# agent-mother.net
KiCad netlist of a schematic drawn in Altium Designer
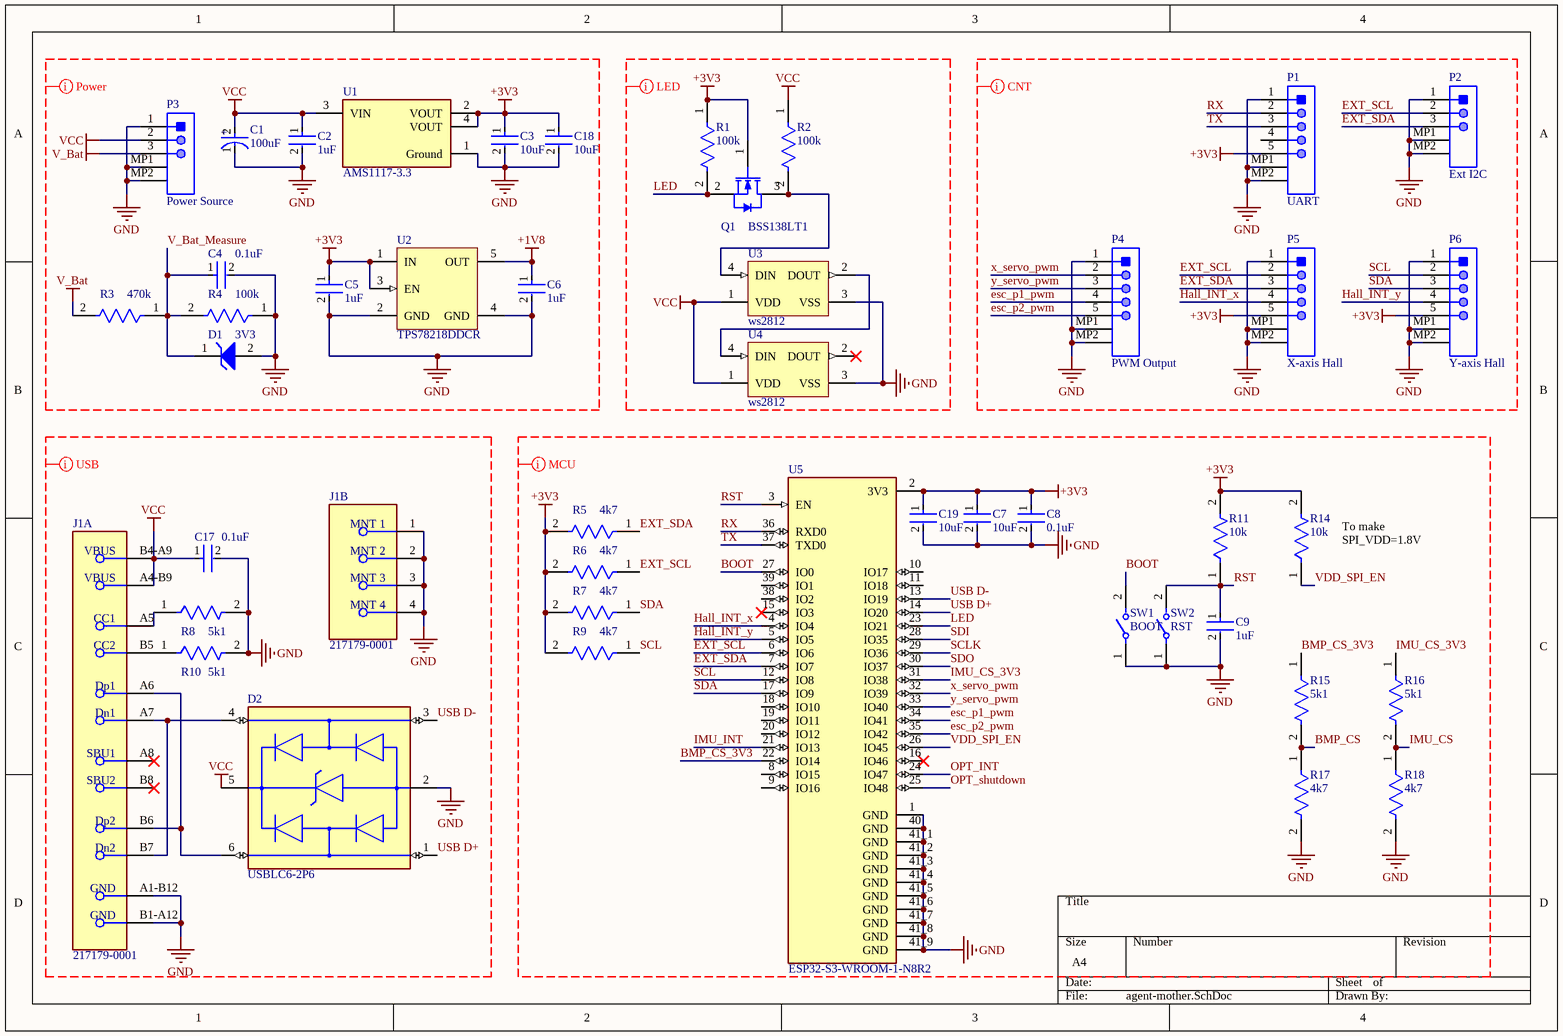
[diagram p0: agent-mother.SchDoc]

(export (version "E")
  (design (tool "Eeschema 10.0.6"))
  (components
    (comp (ref "C1")
      (value "100uF")
      (footprint "FP-T495D107K016ATE125-MFG")
      (description "CAP TANT 100UF 10% 16V 2917")
      (fields (field (name "VOLTAGE") "16V") (field (name "TOLERANCE") "10%"))
      (libsource (lib "Altium Content Vault") (part "a00bbbee19879c290e62620ae7e47b1"))
    )
    (comp (ref "C2")
      (value "1uF")
      (footprint "FP-C0402-BB-MFG")
      (description "CAP CER 1uF 16V X7R 0402")
      (fields
        (field (name "TOLERANCE") "0.1")
        (field (name "OCTOPART") "https://octopart.com/c0402c104k4ractu-kemet-94158")
      )
      (libsource (lib "Altium Content Vault") (part "b4654b650e69147ec39a6b967a45e02"))
    )
    (comp (ref "C3")
      (value "10uF")
      (footprint "FP-C0402-BB-MFG")
      (description "CAP CER 22uF 16V X7R 0402")
      (fields
        (field (name "TOLERANCE") "0.1")
        (field (name "OCTOPART") "https://octopart.com/c0402c104k4ractu-kemet-94158")
      )
      (libsource (lib "Altium Content Vault") (part "b4654b650e69147ec39a6b967a45e02"))
    )
    (comp (ref "C4")
      (value "0.1uF")
      (footprint "FP-C0402-BB-MFG")
      (description "CAP CER 0.1uF 16V X7R 0402")
      (fields
        (field (name "TOLERANCE") "0.1")
        (field (name "OCTOPART") "https://octopart.com/c0402c104k4ractu-kemet-94158")
      )
      (libsource (lib "Altium Content Vault") (part "b4654b650e69147ec39a6b967a45e02"))
    )
    (comp (ref "C5")
      (value "1uF")
      (footprint "FP-C0402-BB-MFG")
      (description "CAP CER 1uF 16V X7R 0402")
      (fields
        (field (name "TOLERANCE") "0.1")
        (field (name "OCTOPART") "https://octopart.com/c0402c104k4ractu-kemet-94158")
      )
      (libsource (lib "Altium Content Vault") (part "b4654b650e69147ec39a6b967a45e02"))
    )
    (comp (ref "C6")
      (value "1uF")
      (footprint "FP-C0402-BB-MFG")
      (description "CAP CER 1uF 16V X7R 0402")
      (fields
        (field (name "TOLERANCE") "0.1")
        (field (name "OCTOPART") "https://octopart.com/c0402c104k4ractu-kemet-94158")
      )
      (libsource (lib "Altium Content Vault") (part "b4654b650e69147ec39a6b967a45e02"))
    )
    (comp (ref "C7")
      (value "10uF")
      (footprint "FP-C0402-BB-MFG")
      (description "CAP CER 22uF 16V X7R 0402")
      (fields
        (field (name "TOLERANCE") "0.1")
        (field (name "OCTOPART") "https://octopart.com/c0402c104k4ractu-kemet-94158")
      )
      (libsource (lib "Altium Content Vault") (part "b4654b650e69147ec39a6b967a45e02"))
    )
    (comp (ref "C8")
      (value "0.1uF")
      (footprint "FP-C0402-BB-MFG")
      (description "CAP CER 0.1uF 16V X7R 0402")
      (fields
        (field (name "TOLERANCE") "0.1")
        (field (name "OCTOPART") "https://octopart.com/c0402c104k4ractu-kemet-94158")
      )
      (libsource (lib "Altium Content Vault") (part "b4654b650e69147ec39a6b967a45e02"))
    )
    (comp (ref "C9")
      (value "1uF")
      (footprint "FP-C0402-BB-MFG")
      (description "CAP CER 1uF 16V X7R 0402")
      (fields
        (field (name "TOLERANCE") "0.1")
        (field (name "OCTOPART") "https://octopart.com/c0402c104k4ractu-kemet-94158")
      )
      (libsource (lib "Altium Content Vault") (part "b4654b650e69147ec39a6b967a45e02"))
    )
    (comp (ref "C17")
      (value "0.1uF")
      (footprint "FP-C0402-BB-MFG")
      (description "CAP CER 0.1uF 16V X7R 0402")
      (fields
        (field (name "TOLERANCE") "0.1")
        (field (name "OCTOPART") "https://octopart.com/c0402c104k4ractu-kemet-94158")
      )
      (libsource (lib "Altium Content Vault") (part "b4654b650e69147ec39a6b967a45e02"))
    )
    (comp (ref "C18")
      (value "10uF")
      (footprint "FP-C0402-BB-MFG")
      (description "CAP CER 22uF 16V X7R 0402")
      (fields
        (field (name "TOLERANCE") "0.1")
        (field (name "OCTOPART") "https://octopart.com/c0402c104k4ractu-kemet-94158")
      )
      (libsource (lib "Altium Content Vault") (part "b4654b650e69147ec39a6b967a45e02"))
    )
    (comp (ref "C19")
      (value "10uF")
      (footprint "FP-C0402-BB-MFG")
      (description "CAP CER 22uF 16V X7R 0402")
      (fields
        (field (name "TOLERANCE") "0.1")
        (field (name "OCTOPART") "https://octopart.com/c0402c104k4ractu-kemet-94158")
      )
      (libsource (lib "Altium Content Vault") (part "b4654b650e69147ec39a6b967a45e02"))
    )
    (comp (ref "D1")
      (value "3V3")
      (footprint "ONSC-SOD-323-2-477-02_V")
      (description "Zener Voltage Regulator, 300 mW, 2-Pin SOD-323, Pb-Free, Tape and Reel")
      (fields (field (name "PARTNUMBER") "MM3Z3V3T1G") (field (name "MANUFACTURER") "On Semiconductor"))
      (libsource (lib "Altium Content Vault") (part "ONSC-K1A2-2"))
    )
    (comp (ref "D2")
      (value "USBLC6-2P6")
      (footprint "SOT-23-6 USBLC6")
      (description "TVS DIODE 5.25V 17V SOT666")
      (libsource (lib "TVMD") (part "USBLC6-2P6"))
    )
    (comp (ref "J1")
      (value "217179-0001")
      (footprint "FP-217179-0001-MFG")
      (description "CONN RCP USB2.0 TYP C 24P SMD RA")
      (libsource (lib "Altium Content Vault") (part "5f86746d156db037abd23105bb3dbc5"))
    )
    (comp (ref "P1")
      (value "UART")
      (footprint "MOLX-52361-0571-5_V")
      (description "Male Header, Pitch 1.25 mm, 1 x 5 Position, Height 3.4 mm, RoHS, Tape and Reel")
      (fields (field (name "MANUFACTURER") "Molex"))
      (libsource (lib "Altium Content Vault") (part "CN-1P-2M-R5"))
    )
    (comp (ref "P2")
      (value "Ext I2C")
      (footprint "FP-53261-0371-MFG")
      (description "CONN HEADER SMD R/A 3POS 1.25MM")
      (fields
        (field (name "MANUFACTURER") "Molex")
        (field (name "OCTOPART") "https://octopart.com/53261-0371-molex-655314")
      )
      (libsource (lib "Components - 19.08.23 - 20.17") (part "CMP-04776-000071-1"))
    )
    (comp (ref "P3")
      (value "Power Source")
      (footprint "FP-53261-0371-MFG")
      (description "CONN HEADER SMD R/A 3POS 1.25MM")
      (fields
        (field (name "MANUFACTURER") "Molex")
        (field (name "OCTOPART") "https://octopart.com/53261-0371-molex-655314")
      )
      (libsource (lib "Components - 19.08.23 - 20.17") (part "CMP-04776-000071-1"))
    )
    (comp (ref "P4")
      (value "PWM Output")
      (footprint "MOLX-52361-0571-5_V")
      (description "Male Header, Pitch 1.25 mm, 1 x 5 Position, Height 3.4 mm, RoHS, Tape and Reel")
      (fields (field (name "MANUFACTURER") "Molex"))
      (libsource (lib "Altium Content Vault") (part "CN-1P-2M-R5"))
    )
    (comp (ref "P5")
      (value "X-axis Hall")
      (footprint "MOLX-52361-0571-5_V")
      (description "Male Header, Pitch 1.25 mm, 1 x 5 Position, Height 3.4 mm, RoHS, Tape and Reel")
      (fields (field (name "MANUFACTURER") "Molex"))
      (libsource (lib "Altium Content Vault") (part "CN-1P-2M-R5"))
    )
    (comp (ref "P6")
      (value "Y-axis Hall")
      (footprint "MOLX-52361-0571-5_V")
      (description "Male Header, Pitch 1.25 mm, 1 x 5 Position, Height 3.4 mm, RoHS, Tape and Reel")
      (fields (field (name "MANUFACTURER") "Molex"))
      (libsource (lib "Altium Content Vault") (part "CN-1P-2M-R5"))
    )
    (comp (ref "Q1")
      (value "BSS138LT1")
      (footprint "ONSC-SOT-23-3-318-08_V")
      (description "Power MOSFET, BSS138LT1, 200 mA, 50 V, N-Channel, 3-Pin SOT-23, Tape and Reel")
      (fields (field (name "MANUFACTURER") "On Semiconductor"))
      (libsource (lib "Altium Content Vault") (part "ONSC-NMOS-G1S2D3-3"))
    )
    (comp (ref "R1")
      (value "100k")
      (footprint "FP-CRCW0402-e3-IPC_A")
      (description "RES Thick Film, 100kΩ, 0.063W, 0402")
      (fields (field (name "TOLERANCE") "5%"))
      (libsource (lib "Altium Content Vault") (part "1029c3af85768c4190bb7ad29bc67b5"))
    )
    (comp (ref "R2")
      (value "100k")
      (footprint "FP-CRCW0402-e3-IPC_A")
      (description "RES Thick Film, 100kΩ, 0.063W, 0402")
      (fields (field (name "TOLERANCE") "5%"))
      (libsource (lib "Altium Content Vault") (part "1029c3af85768c4190bb7ad29bc67b5"))
    )
    (comp (ref "R3")
      (value "470k")
      (footprint "FP-CRCW0402-e3-IPC_A")
      (description "RES Thick Film, 100kΩ, 0.063W, 0402")
      (fields (field (name "TOLERANCE") "5%"))
      (libsource (lib "Altium Content Vault") (part "1029c3af85768c4190bb7ad29bc67b5"))
    )
    (comp (ref "R4")
      (value "100k")
      (footprint "FP-CRCW0402-e3-IPC_A")
      (description "RES Thick Film, 470kΩ, 0.063W, 0402")
      (fields (field (name "TOLERANCE") "5%"))
      (libsource (lib "Altium Content Vault") (part "1029c3af85768c4190bb7ad29bc67b5"))
    )
    (comp (ref "R5")
      (value "4k7")
      (footprint "FP-CRCW0402-e3-IPC_A")
      (description "RES Thick Film, 4k7Ω, 0.063W, 0402")
      (fields (field (name "TOLERANCE") "5%"))
      (libsource (lib "Altium Content Vault") (part "1029c3af85768c4190bb7ad29bc67b5"))
    )
    (comp (ref "R6")
      (value "4k7")
      (footprint "FP-CRCW0402-e3-IPC_A")
      (description "RES Thick Film, 4k7Ω, 0.063W, 0402")
      (fields (field (name "TOLERANCE") "5%"))
      (libsource (lib "Altium Content Vault") (part "1029c3af85768c4190bb7ad29bc67b5"))
    )
    (comp (ref "R7")
      (value "4k7")
      (footprint "FP-CRCW0402-e3-IPC_A")
      (description "RES Thick Film, 4k7Ω, 0.063W, 0402")
      (fields (field (name "TOLERANCE") "5%"))
      (libsource (lib "Altium Content Vault") (part "1029c3af85768c4190bb7ad29bc67b5"))
    )
    (comp (ref "R8")
      (value "5k1")
      (footprint "FP-CRCW0402-e3-IPC_A")
      (description "RES Thick Film, 5k1Ω, 0.063W, 0402")
      (fields (field (name "TOLERANCE") "5%"))
      (libsource (lib "Altium Content Vault") (part "1029c3af85768c4190bb7ad29bc67b5"))
    )
    (comp (ref "R9")
      (value "4k7")
      (footprint "FP-CRCW0402-e3-IPC_A")
      (description "RES Thick Film, 4k7Ω, 0.063W, 0402")
      (fields (field (name "TOLERANCE") "5%"))
      (libsource (lib "Altium Content Vault") (part "1029c3af85768c4190bb7ad29bc67b5"))
    )
    (comp (ref "R10")
      (value "5k1")
      (footprint "FP-CRCW0402-e3-IPC_A")
      (description "RES Thick Film, 5k1Ω, 0.063W, 0402")
      (fields (field (name "TOLERANCE") "5%"))
      (libsource (lib "Altium Content Vault") (part "1029c3af85768c4190bb7ad29bc67b5"))
    )
    (comp (ref "R11")
      (value "10k")
      (footprint "FP-CRCW0402-e3-IPC_A")
      (description "RES Thick Film, 10kΩ, 0.063W, 0402")
      (fields (field (name "TOLERANCE") "5%"))
      (libsource (lib "Altium Content Vault") (part "1029c3af85768c4190bb7ad29bc67b5"))
    )
    (comp (ref "R14")
      (value "10k")
      (footprint "FP-CRCW0402-e3-IPC_A")
      (description "RES Thick Film, 10kΩ, 0.063W, 0402")
      (fields (field (name "TOLERANCE") "5%"))
      (libsource (lib "Altium Content Vault") (part "1029c3af85768c4190bb7ad29bc67b5"))
    )
    (comp (ref "R15")
      (value "5k1")
      (footprint "FP-CRCW0402-e3-IPC_A")
      (description "RES Thick Film, 4k7Ω, 0.063W, 0402")
      (fields (field (name "TOLERANCE") "5%"))
      (libsource (lib "Altium Content Vault") (part "1029c3af85768c4190bb7ad29bc67b5"))
    )
    (comp (ref "R16")
      (value "5k1")
      (footprint "FP-CRCW0402-e3-IPC_A")
      (description "RES Thick Film, 4k7Ω, 0.063W, 0402")
      (fields (field (name "TOLERANCE") "5%"))
      (libsource (lib "Altium Content Vault") (part "1029c3af85768c4190bb7ad29bc67b5"))
    )
    (comp (ref "R17")
      (value "4k7")
      (footprint "FP-CRCW0402-e3-IPC_A")
      (description "RES Thick Film, 4k7Ω, 0.063W, 0402")
      (fields (field (name "TOLERANCE") "5%"))
      (libsource (lib "Altium Content Vault") (part "1029c3af85768c4190bb7ad29bc67b5"))
    )
    (comp (ref "R18")
      (value "4k7")
      (footprint "FP-CRCW0402-e3-IPC_A")
      (description "RES Thick Film, 4k7Ω, 0.063W, 0402")
      (fields (field (name "TOLERANCE") "5%"))
      (libsource (lib "Altium Content Vault") (part "1029c3af85768c4190bb7ad29bc67b5"))
    )
    (comp (ref "SW1")
      (value "BOOT")
      (footprint "FP-B3U-1000P-B-MFG")
      (description "SWITCH TACTILE SPST-NO 0.05A 12V")
      (fields
        (field (name "MANUFACTURER PART NUMBER") "B3U-1000P-B")
        (field (name "OCTOPART") "https://octopart.com/b3u-1000p-b-omron-1057356")
      )
      (libsource (lib "Altium Content Vault") (part "bb27bde45df87f1f469753f287ef5ae"))
    )
    (comp (ref "SW2")
      (value "RST")
      (footprint "FP-B3U-1000P-B-MFG")
      (description "SWITCH TACTILE SPST-NO 0.05A 12V")
      (fields
        (field (name "MANUFACTURER PART NUMBER") "B3U-1000P-B")
        (field (name "OCTOPART") "https://octopart.com/b3u-1000p-b-omron-1057356")
      )
      (libsource (lib "Altium Content Vault") (part "bb27bde45df87f1f469753f287ef5ae"))
    )
    (comp (ref "U1")
      (value "AMS1117-3.3")
      (footprint "FP-AMS1117-IPC_A")
      (description "LDO Voltage Regulators 1A, 3.3V")
      (fields
        (field (name "OCTOPART") "https://octopart.com/ams1117-3.3-advanced+monolithic+systems-25899300")
        (field (name "MANUFACTURER") "Advanced Monolithic Systems")
      )
      (libsource (lib "Altium Content Vault") (part "8bdbb5f8e77002000e30dd2845d0354"))
    )
    (comp (ref "U2")
      (value "TPS78218DDCR")
      (footprint "SOT-23-OT5_M")
      (fields (field (name "MANUFACTURER") "Texas Instruments") (field (name "PARTNUMBER") "TPS78218DRVR"))
      (libsource (lib "TVMD") (part "TI-TPS782XXDRV6-1600X1000TP"))
    )
    (comp (ref "U3")
      (value "ws2812")
      (footprint "ADA-RGB-1655_V")
      (fields (field (name "MANUFACTURER") "Adafruit-Industries-LLC"))
      (libsource (lib "Altium Content Vault") (part "ADA-RGB-1655-4"))
    )
    (comp (ref "U4")
      (value "ws2812")
      (footprint "ADA-RGB-1655_V")
      (fields (field (name "MANUFACTURER") "Adafruit-Industries-LLC"))
      (libsource (lib "Altium Content Vault") (part "ADA-RGB-1655-4"))
    )
    (comp (ref "U5")
      (value "ESP32-S3-WROOM-1-N8R2")
      (footprint "XCVR_ESP32S3WROOM1N8R8")
      (description "Bluetooth, WiFi 802.11b/g/n, Bluetooth v5.0 Transceiver Module 2.4GHz PCB Trace Surface Mount")
      (fields (field (name "MF") "Espressif Systems") (field (name "MP") "ESP32-S3-WROOM-1-N8R8"))
      (libsource (lib "ESP32-S3-WROOM-1-N8R8") (part "ESP32-S3-WROOM-1-N8R8"))
    )
  )
  (nets
    (net (code "1") (name "+1V8") (class "Default")
      (node (ref "C6") (pin "1") (pinfunction "1_1") (pintype "passive"))
      (node (ref "U2") (pin "5") (pinfunction "OUT_5") (pintype "power_in"))
    )
    (net (code "2") (name "+3V3") (class "Default")
      (node (ref "C18") (pin "1") (pinfunction "1_1") (pintype "passive"))
      (node (ref "C19") (pin "1") (pinfunction "1_1") (pintype "passive"))
      (node (ref "C3") (pin "1") (pinfunction "1_1") (pintype "passive"))
      (node (ref "C5") (pin "1") (pinfunction "1_1") (pintype "passive"))
      (node (ref "C7") (pin "1") (pinfunction "1_1") (pintype "passive"))
      (node (ref "C8") (pin "1") (pinfunction "1_1") (pintype "passive"))
      (node (ref "P1") (pin "5") (pinfunction "5_5") (pintype "passive"))
      (node (ref "P5") (pin "5") (pinfunction "5_5") (pintype "passive"))
      (node (ref "P6") (pin "5") (pinfunction "5_5") (pintype "passive"))
      (node (ref "Q1") (pin "1") (pinfunction "G_1") (pintype "passive"))
      (node (ref "R1") (pin "1") (pinfunction "1_1") (pintype "passive"))
      (node (ref "R11") (pin "2") (pinfunction "2_2") (pintype "passive"))
      (node (ref "R14") (pin "2") (pinfunction "2_2") (pintype "passive"))
      (node (ref "R5") (pin "2") (pinfunction "2_2") (pintype "passive"))
      (node (ref "R6") (pin "2") (pinfunction "2_2") (pintype "passive"))
      (node (ref "R7") (pin "2") (pinfunction "2_2") (pintype "passive"))
      (node (ref "R9") (pin "2") (pinfunction "2_2") (pintype "passive"))
      (node (ref "U1") (pin "2") (pinfunction "VOUT_2") (pintype "passive"))
      (node (ref "U1") (pin "4") (pinfunction "VOUT_4") (pintype "passive"))
      (node (ref "U2") (pin "1") (pinfunction "IN_1") (pintype "power_in"))
      (node (ref "U2") (pin "3") (pinfunction "EN_3") (pintype "input"))
      (node (ref "U5") (pin "2") (pinfunction "3V3_2") (pintype "power_in"))
    )
    (net (code "3") (name "/BMP_CS") (class "Default")
      (node (ref "R15") (pin "2") (pinfunction "2_2") (pintype "passive"))
      (node (ref "R17") (pin "1") (pinfunction "1_1") (pintype "passive"))
    )
    (net (code "4") (name "/BMP_CS_3V3") (class "Default")
      (node (ref "R15") (pin "1") (pinfunction "1_1") (pintype "passive"))
      (node (ref "U5") (pin "22") (pinfunction "IO14_22") (pintype "bidirectional"))
    )
    (net (code "5") (name "/BOOT") (class "Default")
      (node (ref "SW1") (pin "2") (pinfunction "2_2") (pintype "passive"))
      (node (ref "U5") (pin "27") (pinfunction "IO0_27") (pintype "bidirectional"))
    )
    (net (code "6") (name "/EXT_SCL") (class "Default")
      (node (ref "P2") (pin "2") (pinfunction "2_2") (pintype "passive"))
      (node (ref "P5") (pin "2") (pinfunction "2_2") (pintype "passive"))
      (node (ref "R6") (pin "1") (pinfunction "1_1") (pintype "passive"))
      (node (ref "U5") (pin "6") (pinfunction "IO6_6") (pintype "bidirectional"))
    )
    (net (code "7") (name "/EXT_SDA") (class "Default")
      (node (ref "P2") (pin "3") (pinfunction "3_3") (pintype "passive"))
      (node (ref "P5") (pin "3") (pinfunction "3_3") (pintype "passive"))
      (node (ref "R5") (pin "1") (pinfunction "1_1") (pintype "passive"))
      (node (ref "U5") (pin "7") (pinfunction "IO7_7") (pintype "bidirectional"))
    )
    (net (code "8") (name "/Hall_INT_x") (class "Default")
      (node (ref "P5") (pin "4") (pinfunction "4_4") (pintype "passive"))
      (node (ref "U5") (pin "4") (pinfunction "IO4_4") (pintype "bidirectional"))
    )
    (net (code "9") (name "/Hall_INT_y") (class "Default")
      (node (ref "P6") (pin "4") (pinfunction "4_4") (pintype "passive"))
      (node (ref "U5") (pin "5") (pinfunction "IO5_5") (pintype "bidirectional"))
    )
    (net (code "10") (name "/IMU_CS") (class "Default")
      (node (ref "R16") (pin "2") (pinfunction "2_2") (pintype "passive"))
      (node (ref "R18") (pin "1") (pinfunction "1_1") (pintype "passive"))
    )
    (net (code "11") (name "/IMU_CS_3V3") (class "Default")
      (node (ref "R16") (pin "1") (pinfunction "1_1") (pintype "passive"))
      (node (ref "U5") (pin "31") (pinfunction "IO38_31") (pintype "bidirectional"))
    )
    (net (code "12") (name "/IMU_INT") (class "Default")
      (node (ref "U5") (pin "21") (pinfunction "IO13_21") (pintype "bidirectional"))
    )
    (net (code "13") (name "/LED") (class "Default")
      (node (ref "Q1") (pin "2") (pinfunction "S_2") (pintype "passive"))
      (node (ref "R1") (pin "2") (pinfunction "2_2") (pintype "passive"))
      (node (ref "U5") (pin "23") (pinfunction "IO21_23") (pintype "bidirectional"))
    )
    (net (code "14") (name "/OPT_INT") (class "Default")
      (node (ref "U5") (pin "24") (pinfunction "IO47_24") (pintype "bidirectional"))
    )
    (net (code "15") (name "/OPT_shutdown") (class "Default")
      (node (ref "U5") (pin "25") (pinfunction "IO48_25") (pintype "bidirectional"))
    )
    (net (code "16") (name "/RST") (class "Default")
      (node (ref "C9") (pin "1") (pinfunction "1_1") (pintype "passive"))
      (node (ref "R11") (pin "1") (pinfunction "1_1") (pintype "passive"))
      (node (ref "SW2") (pin "2") (pinfunction "2_2") (pintype "passive"))
      (node (ref "U5") (pin "3") (pinfunction "EN_3") (pintype "input"))
    )
    (net (code "17") (name "/RX") (class "Default")
      (node (ref "P1") (pin "2") (pinfunction "2_2") (pintype "passive"))
      (node (ref "U5") (pin "36") (pinfunction "RXD0_36") (pintype "bidirectional"))
    )
    (net (code "18") (name "/SCL") (class "Default")
      (node (ref "P6") (pin "2") (pinfunction "2_2") (pintype "passive"))
      (node (ref "R9") (pin "1") (pinfunction "1_1") (pintype "passive"))
      (node (ref "U5") (pin "12") (pinfunction "IO8_12") (pintype "bidirectional"))
    )
    (net (code "19") (name "/SCLK") (class "Default")
      (node (ref "U5") (pin "29") (pinfunction "IO36_29") (pintype "bidirectional"))
    )
    (net (code "20") (name "/SDA") (class "Default")
      (node (ref "P6") (pin "3") (pinfunction "3_3") (pintype "passive"))
      (node (ref "R7") (pin "1") (pinfunction "1_1") (pintype "passive"))
      (node (ref "U5") (pin "17") (pinfunction "IO9_17") (pintype "bidirectional"))
    )
    (net (code "21") (name "/SDI") (class "Default")
      (node (ref "U5") (pin "28") (pinfunction "IO35_28") (pintype "bidirectional"))
    )
    (net (code "22") (name "/SDO") (class "Default")
      (node (ref "U5") (pin "30") (pinfunction "IO37_30") (pintype "bidirectional"))
    )
    (net (code "23") (name "/TX") (class "Default")
      (node (ref "P1") (pin "3") (pinfunction "3_3") (pintype "passive"))
      (node (ref "U5") (pin "37") (pinfunction "TXD0_37") (pintype "bidirectional"))
    )
    (net (code "24") (name "/USB D+") (class "Default")
      (node (ref "D2") (pin "1") (pinfunction "I/O1_1") (pintype "bidirectional"))
      (node (ref "U5") (pin "14") (pinfunction "IO20_14") (pintype "bidirectional"))
    )
    (net (code "25") (name "/USB D-") (class "Default")
      (node (ref "D2") (pin "3") (pinfunction "I/O2_3") (pintype "bidirectional"))
      (node (ref "U5") (pin "13") (pinfunction "IO19_13") (pintype "bidirectional"))
    )
    (net (code "26") (name "/VDD_SPI_EN") (class "Default")
      (node (ref "R14") (pin "1") (pinfunction "1_1") (pintype "passive"))
      (node (ref "U5") (pin "26") (pinfunction "IO45_26") (pintype "bidirectional"))
    )
    (net (code "27") (name "/V_Bat_Measure") (class "Default")
      (node (ref "C4") (pin "1") (pinfunction "1_1") (pintype "passive"))
      (node (ref "D1") (pin "1") (pinfunction "K_1") (pintype "passive"))
      (node (ref "R3") (pin "1") (pinfunction "1_1") (pintype "passive"))
      (node (ref "R4") (pin "2") (pinfunction "2_2") (pintype "passive"))
    )
    (net (code "28") (name "/esc_p1_pwm") (class "Default")
      (node (ref "P4") (pin "4") (pinfunction "4_4") (pintype "passive"))
      (node (ref "U5") (pin "34") (pinfunction "IO41_34") (pintype "bidirectional"))
    )
    (net (code "29") (name "/esc_p2_pwm") (class "Default")
      (node (ref "P4") (pin "5") (pinfunction "5_5") (pintype "passive"))
      (node (ref "U5") (pin "35") (pinfunction "IO42_35") (pintype "bidirectional"))
    )
    (net (code "30") (name "/x_servo_pwm") (class "Default")
      (node (ref "P4") (pin "2") (pinfunction "2_2") (pintype "passive"))
      (node (ref "U5") (pin "32") (pinfunction "IO39_32") (pintype "bidirectional"))
    )
    (net (code "31") (name "/y_servo_pwm") (class "Default")
      (node (ref "P4") (pin "3") (pinfunction "3_3") (pintype "passive"))
      (node (ref "U5") (pin "33") (pinfunction "IO40_33") (pintype "bidirectional"))
    )
    (net (code "32") (name "GND") (class "Default")
      (node (ref "C1") (pin "1") (pinfunction "C_1") (pintype "passive"))
      (node (ref "C17") (pin "2") (pinfunction "2_2") (pintype "passive"))
      (node (ref "C18") (pin "2") (pinfunction "2_2") (pintype "passive"))
      (node (ref "C19") (pin "2") (pinfunction "2_2") (pintype "passive"))
      (node (ref "C2") (pin "2") (pinfunction "2_2") (pintype "passive"))
      (node (ref "C3") (pin "2") (pinfunction "2_2") (pintype "passive"))
      (node (ref "C4") (pin "2") (pinfunction "2_2") (pintype "passive"))
      (node (ref "C5") (pin "2") (pinfunction "2_2") (pintype "passive"))
      (node (ref "C6") (pin "2") (pinfunction "2_2") (pintype "passive"))
      (node (ref "C7") (pin "2") (pinfunction "2_2") (pintype "passive"))
      (node (ref "C8") (pin "2") (pinfunction "2_2") (pintype "passive"))
      (node (ref "C9") (pin "2") (pinfunction "2_2") (pintype "passive"))
      (node (ref "D1") (pin "2") (pinfunction "A_2") (pintype "passive"))
      (node (ref "D2") (pin "2") (pinfunction "GND_2") (pintype "power_in"))
      (node (ref "J1") (pin "1") (pinfunction "MNT_1_1") (pintype "passive"))
      (node (ref "J1") (pin "2") (pinfunction "MNT_2_2") (pintype "passive"))
      (node (ref "J1") (pin "3") (pinfunction "MNT_3_3") (pintype "passive"))
      (node (ref "J1") (pin "4") (pinfunction "MNT_4_4") (pintype "passive"))
      (node (ref "J1") (pin "A1-B12") (pinfunction "GND_A1-B12") (pintype "power_in"))
      (node (ref "J1") (pin "B1-A12") (pinfunction "GND_B1-A12") (pintype "power_in"))
      (node (ref "P1") (pin "1") (pinfunction "1_1") (pintype "passive"))
      (node (ref "P1") (pin "MP1") (pinfunction "MP1_MP1") (pintype "passive"))
      (node (ref "P1") (pin "MP2") (pinfunction "MP2_MP2") (pintype "passive"))
      (node (ref "P2") (pin "1") (pinfunction "1_1") (pintype "passive"))
      (node (ref "P2") (pin "MP1") (pinfunction "MP1_MP1") (pintype "passive"))
      (node (ref "P2") (pin "MP2") (pinfunction "MP2_MP2") (pintype "passive"))
      (node (ref "P3") (pin "1") (pinfunction "1_1") (pintype "passive"))
      (node (ref "P3") (pin "MP1") (pinfunction "MP1_MP1") (pintype "passive"))
      (node (ref "P3") (pin "MP2") (pinfunction "MP2_MP2") (pintype "passive"))
      (node (ref "P4") (pin "1") (pinfunction "1_1") (pintype "passive"))
      (node (ref "P4") (pin "MP1") (pinfunction "MP1_MP1") (pintype "passive"))
      (node (ref "P4") (pin "MP2") (pinfunction "MP2_MP2") (pintype "passive"))
      (node (ref "P5") (pin "1") (pinfunction "1_1") (pintype "passive"))
      (node (ref "P5") (pin "MP1") (pinfunction "MP1_MP1") (pintype "passive"))
      (node (ref "P5") (pin "MP2") (pinfunction "MP2_MP2") (pintype "passive"))
      (node (ref "P6") (pin "1") (pinfunction "1_1") (pintype "passive"))
      (node (ref "P6") (pin "MP1") (pinfunction "MP1_MP1") (pintype "passive"))
      (node (ref "P6") (pin "MP2") (pinfunction "MP2_MP2") (pintype "passive"))
      (node (ref "R10") (pin "2") (pinfunction "2_2") (pintype "passive"))
      (node (ref "R17") (pin "2") (pinfunction "2_2") (pintype "passive"))
      (node (ref "R18") (pin "2") (pinfunction "2_2") (pintype "passive"))
      (node (ref "R4") (pin "1") (pinfunction "1_1") (pintype "passive"))
      (node (ref "R8") (pin "2") (pinfunction "2_2") (pintype "passive"))
      (node (ref "SW1") (pin "1") (pinfunction "1_1") (pintype "passive"))
      (node (ref "SW2") (pin "1") (pinfunction "1_1") (pintype "passive"))
      (node (ref "U1") (pin "1") (pinfunction "Ground_1") (pintype "power_in"))
      (node (ref "U2") (pin "2") (pinfunction "GND_2") (pintype "power_in"))
      (node (ref "U2") (pin "4") (pinfunction "GND_4") (pintype "power_in"))
      (node (ref "U3") (pin "3") (pinfunction "VSS_3") (pintype "power_in"))
      (node (ref "U4") (pin "3") (pinfunction "VSS_3") (pintype "power_in"))
      (node (ref "U5") (pin "1") (pinfunction "GND_1") (pintype "power_in"))
      (node (ref "U5") (pin "40") (pinfunction "GND_40") (pintype "power_in"))
      (node (ref "U5") (pin "41_1") (pinfunction "GND_41_1") (pintype "power_in"))
      (node (ref "U5") (pin "41_2") (pinfunction "GND_41_2") (pintype "power_in"))
      (node (ref "U5") (pin "41_3") (pinfunction "GND_41_3") (pintype "power_in"))
      (node (ref "U5") (pin "41_4") (pinfunction "GND_41_4") (pintype "power_in"))
      (node (ref "U5") (pin "41_5") (pinfunction "GND_41_5") (pintype "power_in"))
      (node (ref "U5") (pin "41_6") (pinfunction "GND_41_6") (pintype "power_in"))
      (node (ref "U5") (pin "41_7") (pinfunction "GND_41_7") (pintype "power_in"))
      (node (ref "U5") (pin "41_8") (pinfunction "GND_41_8") (pintype "power_in"))
      (node (ref "U5") (pin "41_9") (pinfunction "GND_41_9") (pintype "power_in"))
    )
    (net (code "33") (name "Net-(J1A-CC1)") (class "Default")
      (node (ref "J1") (pin "A5") (pinfunction "CC1_A5") (pintype "passive"))
      (node (ref "R8") (pin "1") (pinfunction "1_1") (pintype "passive"))
    )
    (net (code "34") (name "Net-(J1A-CC2)") (class "Default")
      (node (ref "J1") (pin "B5") (pinfunction "CC2_B5") (pintype "passive"))
      (node (ref "R10") (pin "1") (pinfunction "1_1") (pintype "passive"))
    )
    (net (code "35") (name "Net-(J1A-Dn1)") (class "Default")
      (node (ref "D2") (pin "4") (pinfunction "I/O2_4") (pintype "bidirectional"))
      (node (ref "J1") (pin "A7") (pinfunction "Dn1_A7") (pintype "passive"))
      (node (ref "J1") (pin "B7") (pinfunction "Dn2_B7") (pintype "passive"))
    )
    (net (code "36") (name "Net-(J1A-Dp1)") (class "Default")
      (node (ref "D2") (pin "6") (pinfunction "I/O1_6") (pintype "bidirectional"))
      (node (ref "J1") (pin "A6") (pinfunction "Dp1_A6") (pintype "passive"))
      (node (ref "J1") (pin "B6") (pinfunction "Dp2_B6") (pintype "passive"))
    )
    (net (code "37") (name "Net-(Q1-D)") (class "Default")
      (node (ref "Q1") (pin "3") (pinfunction "D_3") (pintype "passive"))
      (node (ref "R2") (pin "2") (pinfunction "2_2") (pintype "passive"))
      (node (ref "U3") (pin "4") (pinfunction "DIN_4") (pintype "input"))
    )
    (net (code "38") (name "Net-(U3-DOUT)") (class "Default")
      (node (ref "U3") (pin "2") (pinfunction "DOUT_2") (pintype "output"))
      (node (ref "U4") (pin "4") (pinfunction "DIN_4") (pintype "input"))
    )
    (net (code "39") (name "VCC") (class "Default")
      (node (ref "C1") (pin "2") (pinfunction "A_2") (pintype "passive"))
      (node (ref "C17") (pin "1") (pinfunction "1_1") (pintype "passive"))
      (node (ref "C2") (pin "1") (pinfunction "1_1") (pintype "passive"))
      (node (ref "D2") (pin "5") (pinfunction "VBUS_5") (pintype "power_in"))
      (node (ref "J1") (pin "A4-B9") (pinfunction "VBUS_A4-B9") (pintype "power_in"))
      (node (ref "J1") (pin "B4-A9") (pinfunction "VBUS_B4-A9") (pintype "power_in"))
      (node (ref "P3") (pin "2") (pinfunction "2_2") (pintype "passive"))
      (node (ref "R2") (pin "1") (pinfunction "1_1") (pintype "passive"))
      (node (ref "U1") (pin "3") (pinfunction "VIN_3") (pintype "power_in"))
      (node (ref "U3") (pin "1") (pinfunction "VDD_1") (pintype "power_in"))
      (node (ref "U4") (pin "1") (pinfunction "VDD_1") (pintype "power_in"))
    )
    (net (code "40") (name "V_Bat") (class "Default")
      (node (ref "P3") (pin "3") (pinfunction "3_3") (pintype "passive"))
      (node (ref "R3") (pin "2") (pinfunction "2_2") (pintype "passive"))
    )
    (net (code "41") (name "unconnected-(J1A-SBU1-PadA8)") (class "Default")
      (node (ref "J1") (pin "A8") (pinfunction "SBU1_A8") (pintype "passive+no_connect"))
    )
    (net (code "42") (name "unconnected-(J1A-SBU2-PadB8)") (class "Default")
      (node (ref "J1") (pin "B8") (pinfunction "SBU2_B8") (pintype "passive+no_connect"))
    )
    (net (code "43") (name "unconnected-(P1-Pad4)") (class "Default")
      (node (ref "P1") (pin "4") (pinfunction "4_4") (pintype "passive"))
    )
    (net (code "44") (name "unconnected-(U4-DOUT-Pad2)") (class "Default")
      (node (ref "U4") (pin "2") (pinfunction "DOUT_2") (pintype "output+no_connect"))
    )
    (net (code "45") (name "unconnected-(U5-IO1-Pad39)") (class "Default")
      (node (ref "U5") (pin "39") (pinfunction "IO1_39") (pintype "bidirectional"))
    )
    (net (code "46") (name "unconnected-(U5-IO2-Pad38)") (class "Default")
      (node (ref "U5") (pin "38") (pinfunction "IO2_38") (pintype "bidirectional"))
    )
    (net (code "47") (name "unconnected-(U5-IO3-Pad15)") (class "Default")
      (node (ref "U5") (pin "15") (pinfunction "IO3_15") (pintype "bidirectional+no_connect"))
    )
    (net (code "48") (name "unconnected-(U5-IO10-Pad18)") (class "Default")
      (node (ref "U5") (pin "18") (pinfunction "IO10_18") (pintype "bidirectional"))
    )
    (net (code "49") (name "unconnected-(U5-IO11-Pad19)") (class "Default")
      (node (ref "U5") (pin "19") (pinfunction "IO11_19") (pintype "bidirectional"))
    )
    (net (code "50") (name "unconnected-(U5-IO12-Pad20)") (class "Default")
      (node (ref "U5") (pin "20") (pinfunction "IO12_20") (pintype "bidirectional"))
    )
    (net (code "51") (name "unconnected-(U5-IO15-Pad8)") (class "Default")
      (node (ref "U5") (pin "8") (pinfunction "IO15_8") (pintype "bidirectional"))
    )
    (net (code "52") (name "unconnected-(U5-IO16-Pad9)") (class "Default")
      (node (ref "U5") (pin "9") (pinfunction "IO16_9") (pintype "bidirectional"))
    )
    (net (code "53") (name "unconnected-(U5-IO17-Pad10)") (class "Default")
      (node (ref "U5") (pin "10") (pinfunction "IO17_10") (pintype "bidirectional"))
    )
    (net (code "54") (name "unconnected-(U5-IO18-Pad11)") (class "Default")
      (node (ref "U5") (pin "11") (pinfunction "IO18_11") (pintype "bidirectional"))
    )
    (net (code "55") (name "unconnected-(U5-IO46-Pad16)") (class "Default")
      (node (ref "U5") (pin "16") (pinfunction "IO46_16") (pintype "bidirectional+no_connect"))
    )
  )
)
